# Sheet1.net
KiCad netlist of a schematic drawn in Altium Designer
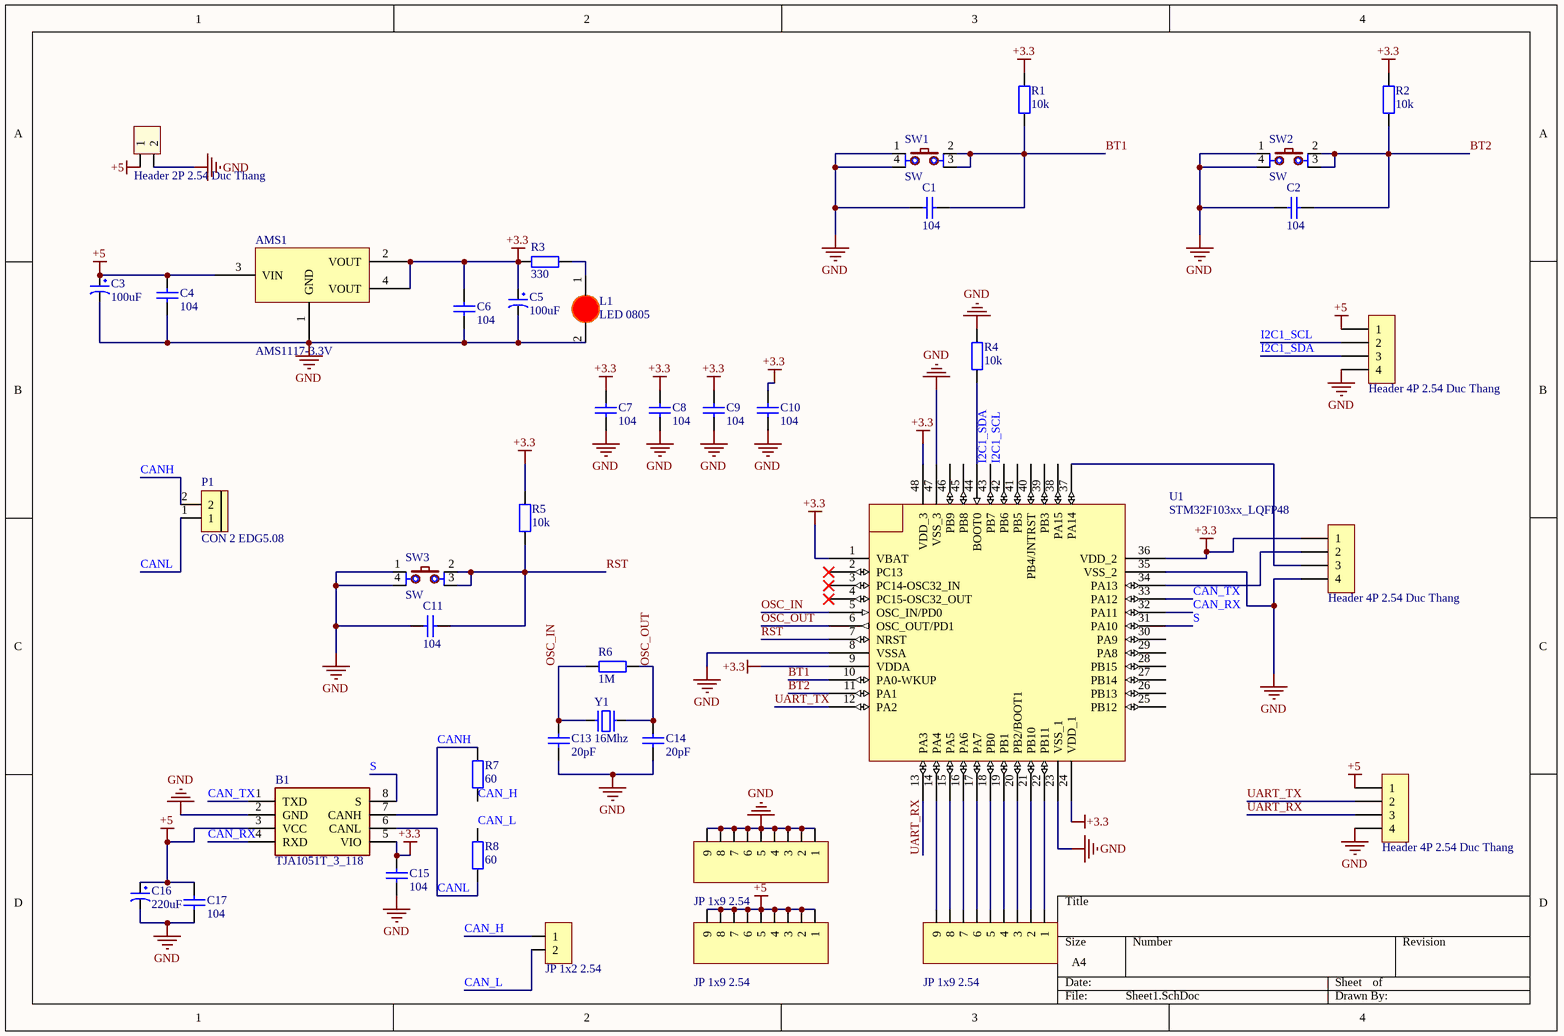
[diagram p0: Sheet1.SchDoc]

(export (version "E")
  (design (tool "Eeschema 10.0.6"))
  (components
    (comp (ref "AMS1")
      (value "AMS1117-3.3V")
      (footprint "SOT223")
      (description "Dán")
      (libsource (lib "Altium_Lib_by_KhueNguyenCreator") (part "AMS1117 SMD"))
    )
    (comp (ref "B1")
      (value "TJA1051T_3_118")
      (footprint "SOIC127P600X175-8N")
      (description "CAN Interface IC Hi Spd CAN Transcvr 4.5V-5.5V 250ns")
      (fields
        (field (name "MOUSER PART NUMBER") "771-TJA1051T3118")
        (field (name "MANUFACTURER_PART_NUMBER") "TJA1051T/3,118")
      )
      (libsource (lib "TJA1051T_3_118") (part "TJA1051T_3_118"))
    )
    (comp (ref "C1")
      (value "104")
      (footprint "tu 0805")
      (description "Dán")
      (libsource (lib "Altium_Lib_by_KhueNguyenCreator") (part "Tu 0805 104 50V 10%"))
    )
    (comp (ref "C2")
      (value "104")
      (footprint "tu 0805")
      (description "Dán")
      (libsource (lib "Altium_Lib_by_KhueNguyenCreator") (part "Tu 0805 104 50V 10%"))
    )
    (comp (ref "C3")
      (value "100uF")
      (footprint "tu hoa 5mm")
      (description "Cắm")
      (libsource (lib "Altium_Lib_by_KhueNguyenCreator") (part "Tu Hoa 100uF 16V 5x7"))
    )
    (comp (ref "C4")
      (value "104")
      (footprint "tu 0805")
      (description "Dán")
      (libsource (lib "Altium_Lib_by_KhueNguyenCreator") (part "Tu 0805 104 50V 10%"))
    )
    (comp (ref "C5")
      (value "100uF")
      (footprint "tu hoa 5mm")
      (description "Cắm")
      (libsource (lib "Altium_Lib_by_KhueNguyenCreator") (part "Tu Hoa 100uF 16V 5x7"))
    )
    (comp (ref "C6")
      (value "104")
      (footprint "tu 0805")
      (description "Dán")
      (libsource (lib "Altium_Lib_by_KhueNguyenCreator") (part "Tu 0805 104 50V 10%"))
    )
    (comp (ref "C7")
      (value "104")
      (footprint "tu 0805")
      (description "Dán")
      (libsource (lib "Altium_Lib_by_KhueNguyenCreator") (part "Tu 0805 104 50V 10%"))
    )
    (comp (ref "C8")
      (value "104")
      (footprint "tu 0805")
      (description "Dán")
      (libsource (lib "Altium_Lib_by_KhueNguyenCreator") (part "Tu 0805 104 50V 10%"))
    )
    (comp (ref "C9")
      (value "104")
      (footprint "tu 0805")
      (description "Dán")
      (libsource (lib "Altium_Lib_by_KhueNguyenCreator") (part "Tu 0805 104 50V 10%"))
    )
    (comp (ref "C10")
      (value "104")
      (footprint "tu 0805")
      (description "Dán")
      (libsource (lib "Altium_Lib_by_KhueNguyenCreator") (part "Tu 0805 104 50V 10%"))
    )
    (comp (ref "C11")
      (value "104")
      (footprint "tu 0805")
      (description "Dán")
      (libsource (lib "Altium_Lib_by_KhueNguyenCreator") (part "Tu 0805 104 50V 10%"))
    )
    (comp (ref "C13")
      (value "20pF")
      (footprint "tu 0805")
      (description "Dán")
      (libsource (lib "Altium_Lib_by_KhueNguyenCreator") (part "Tu 0805 104 50V 10%"))
    )
    (comp (ref "C14")
      (value "20pF")
      (footprint "tu 0805")
      (description "Dán")
      (libsource (lib "Altium_Lib_by_KhueNguyenCreator") (part "Tu 0805 104 50V 10%"))
    )
    (comp (ref "C15")
      (value "104")
      (footprint "tu 0805")
      (description "Dán")
      (libsource (lib "Altium_Lib_by_KhueNguyenCreator") (part "Tu 0805 104 50V 10%"))
    )
    (comp (ref "C16")
      (value "220uF")
      (footprint "tu hoa 16mm")
      (description "Cắm")
      (libsource (lib "Altium_Lib_by_KhueNguyenCreator") (part "Tu Hoa 220uF 200V 15x35"))
    )
    (comp (ref "C17")
      (value "104")
      (footprint "tu 0805")
      (description "Dán")
      (libsource (lib "Altium_Lib_by_KhueNguyenCreator") (part "Tu 0805 104 50V 10%"))
    )
    (comp (ref "H1")
      (value "Header 2P 2.54 Duc Thang")
      (footprint "XH2.54M-2")
      (description "Cắm")
      (libsource (lib "Altium_Lib_by_KhueNguyenCreator") (part "Header 2P 2.54 Duc Thang"))
    )
    (comp (ref "H2")
      (value "Header 4P 2.54 Duc Thang")
      (footprint "XH2.54M-4")
      (description "Cắm")
      (libsource (lib "Altium_Lib_by_KhueNguyenCreator") (part "Header 4P 2.54 Duc Thang"))
    )
    (comp (ref "H3")
      (value "Header 4P 2.54 Duc Thang")
      (footprint "XH2.54M-4")
      (description "Cắm")
      (libsource (lib "Altium_Lib_by_KhueNguyenCreator") (part "Header 4P 2.54 Duc Thang"))
    )
    (comp (ref "H4")
      (value "Header 4P 2.54 Duc Thang")
      (footprint "XH2.54M-4")
      (description "Cắm")
      (libsource (lib "Altium_Lib_by_KhueNguyenCreator") (part "Header 4P 2.54 Duc Thang"))
    )
    (comp (ref "JP1")
      (value "JP 1x9 2.54")
      (footprint "JP 1x9 DT")
      (description "Cắm")
      (libsource (lib "Altium_Lib_by_KhueNguyenCreator") (part "JP 1x9 2.54 Duc Thang"))
    )
    (comp (ref "JP2")
      (value "JP 1x9 2.54")
      (footprint "JP 1x9 DT")
      (description "Cắm")
      (libsource (lib "Altium_Lib_by_KhueNguyenCreator") (part "JP 1x9 2.54 Duc Thang"))
    )
    (comp (ref "JP3")
      (value "JP 1x9 2.54")
      (footprint "JP 1x9 DT")
      (description "Cắm")
      (libsource (lib "Altium_Lib_by_KhueNguyenCreator") (part "JP 1x9 2.54 Duc Thang"))
    )
    (comp (ref "JP5")
      (value "JP 1x2 2.54")
      (footprint "JP 1x2 DT")
      (description "Cắm")
      (libsource (lib "Altium_Lib_by_KhueNguyenCreator") (part "JP 1x2 2.54 Duc Thang"))
    )
    (comp (ref "L1")
      (value "LED 0805")
      (footprint "LED-0805-Red")
      (description "Dán")
      (libsource (lib "Altium_Lib_by_KhueNguyenCreator") (part "LED 0805 Do"))
    )
    (comp (ref "P1")
      (value "CON 2 EDG5.08")
      (footprint "CON 2 2EDG5.08")
      (description "Cắm")
      (libsource (lib "Altium_Lib_by_KhueNguyenCreator") (part "CON 2 EDG5.08"))
    )
    (comp (ref "R1")
      (value "10k")
      (footprint "tro smd 0805")
      (description "Dán")
      (libsource (lib "Altium_Lib_by_KhueNguyenCreator") (part "Tro 0805 1% 18k"))
    )
    (comp (ref "R2")
      (value "10k")
      (footprint "tro smd 0805")
      (description "Dán")
      (libsource (lib "Altium_Lib_by_KhueNguyenCreator") (part "Tro 0805 1% 18k"))
    )
    (comp (ref "R3")
      (value "330")
      (footprint "tro smd 0805")
      (description "Dán")
      (libsource (lib "Altium_Lib_by_KhueNguyenCreator") (part "Tro 0805 1% 18k"))
    )
    (comp (ref "R4")
      (value "10k")
      (footprint "tro smd 0805")
      (description "Dán")
      (libsource (lib "Altium_Lib_by_KhueNguyenCreator") (part "Tro 0805 1% 18k"))
    )
    (comp (ref "R5")
      (value "10k")
      (footprint "tro smd 0805")
      (description "Dán")
      (libsource (lib "Altium_Lib_by_KhueNguyenCreator") (part "Tro 0805 1% 18k"))
    )
    (comp (ref "R6")
      (value "1M")
      (footprint "tro smd 0805")
      (description "Dán")
      (libsource (lib "Altium_Lib_by_KhueNguyenCreator") (part "Tro 0805 1% 18k"))
    )
    (comp (ref "R7")
      (value "60")
      (footprint "tro smd 0805")
      (description "Dán")
      (libsource (lib "Altium_Lib_by_KhueNguyenCreator") (part "Tro 0805 1% 18k"))
    )
    (comp (ref "R8")
      (value "60")
      (footprint "tro smd 0805")
      (description "Dán")
      (libsource (lib "Altium_Lib_by_KhueNguyenCreator") (part "Tro 0805 1% 18k"))
    )
    (comp (ref "SW1")
      (value "SW")
      (footprint "SW2-DIP")
      (description "Switch button 4 pin")
      (libsource (lib "LIBRARY1") (part "SW4"))
    )
    (comp (ref "SW2")
      (value "SW")
      (footprint "SW2-DIP")
      (description "Switch button 4 pin")
      (libsource (lib "LIBRARY1") (part "SW4"))
    )
    (comp (ref "SW3")
      (value "SW")
      (footprint "SW2-DIP")
      (description "Switch button 4 pin")
      (libsource (lib "LIBRARY1") (part "SW4"))
    )
    (comp (ref "U1")
      (value "STM32F103xx_LQFP48")
      (footprint "STM32_LQPF48")
      (fields (field (name "PUBLISHER") "Altium Limited"))
      (libsource (lib "Altium_Lib_by_KhueNguyenCreator") (part "STM32F103xx_LQFP48"))
    )
    (comp (ref "Y1")
      (value "16Mhz")
      (footprint "Thach Anh 2 chan cam")
      (description "Crystal For all Crystal 2pin.")
      (libsource (lib "Altium_Lib_by_KhueNguyenCreator") (part "Thach Anh 2 chan Cam"))
    )
  )
  (nets
    (net (code "1") (name "+3.3") (class "Default")
      (node (ref "AMS1") (pin "2") (pinfunction "VOUT_2") (pintype "passive"))
      (node (ref "AMS1") (pin "4") (pinfunction "VOUT_4") (pintype "passive"))
      (node (ref "B1") (pin "5") (pinfunction "VIO_5") (pintype "passive"))
      (node (ref "C10") (pin "1") (pinfunction "1_1") (pintype "passive"))
      (node (ref "C15") (pin "1") (pinfunction "1_1") (pintype "passive"))
      (node (ref "C5") (pin "1") (pinfunction "1_1") (pintype "passive"))
      (node (ref "C6") (pin "1") (pinfunction "1_1") (pintype "passive"))
      (node (ref "C7") (pin "1") (pinfunction "1_1") (pintype "passive"))
      (node (ref "C8") (pin "1") (pinfunction "1_1") (pintype "passive"))
      (node (ref "C9") (pin "1") (pinfunction "1_1") (pintype "passive"))
      (node (ref "H3") (pin "1") (pinfunction "1_1") (pintype "passive"))
      (node (ref "R1") (pin "2") (pinfunction "2_2") (pintype "passive"))
      (node (ref "R2") (pin "2") (pinfunction "2_2") (pintype "passive"))
      (node (ref "R3") (pin "2") (pinfunction "2_2") (pintype "passive"))
      (node (ref "R5") (pin "2") (pinfunction "2_2") (pintype "passive"))
      (node (ref "U1") (pin "1") (pinfunction "VBAT_1") (pintype "power_in"))
      (node (ref "U1") (pin "24") (pinfunction "VDD_1_24") (pintype "power_in"))
      (node (ref "U1") (pin "36") (pinfunction "VDD_2_36") (pintype "power_in"))
      (node (ref "U1") (pin "48") (pinfunction "VDD_3_48") (pintype "power_in"))
      (node (ref "U1") (pin "9") (pinfunction "VDDA_9") (pintype "power_in"))
    )
    (net (code "2") (name "+5") (class "Default")
      (node (ref "AMS1") (pin "3") (pinfunction "VIN_3") (pintype "passive"))
      (node (ref "B1") (pin "3") (pinfunction "VCC_3") (pintype "passive"))
      (node (ref "C16") (pin "1") (pinfunction "1_1") (pintype "passive"))
      (node (ref "C17") (pin "1") (pinfunction "1_1") (pintype "passive"))
      (node (ref "C3") (pin "1") (pinfunction "1_1") (pintype "passive"))
      (node (ref "C4") (pin "1") (pinfunction "1_1") (pintype "passive"))
      (node (ref "H1") (pin "1") (pinfunction "1_1") (pintype "passive"))
      (node (ref "H2") (pin "1") (pinfunction "1_1") (pintype "passive"))
      (node (ref "H4") (pin "1") (pinfunction "1_1") (pintype "passive"))
      (node (ref "JP3") (pin "1") (pinfunction "1_1") (pintype "passive"))
      (node (ref "JP3") (pin "2") (pinfunction "2_2") (pintype "passive"))
      (node (ref "JP3") (pin "3") (pinfunction "3_3") (pintype "passive"))
      (node (ref "JP3") (pin "4") (pinfunction "4_4") (pintype "passive"))
      (node (ref "JP3") (pin "5") (pinfunction "5_5") (pintype "passive"))
      (node (ref "JP3") (pin "6") (pinfunction "6_6") (pintype "passive"))
      (node (ref "JP3") (pin "7") (pinfunction "7_7") (pintype "passive"))
      (node (ref "JP3") (pin "8") (pinfunction "8_8") (pintype "passive"))
      (node (ref "JP3") (pin "9") (pinfunction "9_9") (pintype "passive"))
    )
    (net (code "3") (name "/BT1") (class "Default")
      (node (ref "C1") (pin "2") (pinfunction "2_2") (pintype "passive"))
      (node (ref "R1") (pin "1") (pinfunction "1_1") (pintype "passive"))
      (node (ref "SW1") (pin "2") (pinfunction "2_2") (pintype "passive"))
      (node (ref "SW1") (pin "3") (pinfunction "3_3") (pintype "passive"))
      (node (ref "U1") (pin "10") (pinfunction "PA0-WKUP_10") (pintype "bidirectional"))
    )
    (net (code "4") (name "/BT2") (class "Default")
      (node (ref "C2") (pin "2") (pinfunction "2_2") (pintype "passive"))
      (node (ref "R2") (pin "1") (pinfunction "1_1") (pintype "passive"))
      (node (ref "SW2") (pin "2") (pinfunction "2_2") (pintype "passive"))
      (node (ref "SW2") (pin "3") (pinfunction "3_3") (pintype "passive"))
      (node (ref "U1") (pin "11") (pinfunction "PA1_11") (pintype "bidirectional"))
    )
    (net (code "5") (name "/CANH") (class "Default")
      (node (ref "B1") (pin "7") (pinfunction "CANH_7") (pintype "passive"))
      (node (ref "P1") (pin "2") (pinfunction "2_2") (pintype "passive"))
      (node (ref "R7") (pin "2") (pinfunction "2_2") (pintype "passive"))
    )
    (net (code "6") (name "/CANL") (class "Default")
      (node (ref "B1") (pin "6") (pinfunction "CANL_6") (pintype "passive"))
      (node (ref "P1") (pin "1") (pinfunction "1_1") (pintype "passive"))
      (node (ref "R8") (pin "1") (pinfunction "1_1") (pintype "passive"))
    )
    (net (code "7") (name "/CAN_H") (class "Default")
      (node (ref "JP5") (pin "1") (pinfunction "1_1") (pintype "passive"))
      (node (ref "R7") (pin "1") (pinfunction "1_1") (pintype "passive"))
    )
    (net (code "8") (name "/CAN_L") (class "Default")
      (node (ref "JP5") (pin "2") (pinfunction "2_2") (pintype "passive"))
      (node (ref "R8") (pin "2") (pinfunction "2_2") (pintype "passive"))
    )
    (net (code "9") (name "/CAN_RX") (class "Default")
      (node (ref "B1") (pin "4") (pinfunction "RXD_4") (pintype "passive"))
      (node (ref "U1") (pin "32") (pinfunction "PA11_32") (pintype "bidirectional"))
    )
    (net (code "10") (name "/CAN_TX") (class "Default")
      (node (ref "B1") (pin "1") (pinfunction "TXD_1") (pintype "passive"))
      (node (ref "U1") (pin "33") (pinfunction "PA12_33") (pintype "bidirectional"))
    )
    (net (code "11") (name "/I2C1_SCL") (class "Default")
      (node (ref "H2") (pin "2") (pinfunction "2_2") (pintype "passive"))
      (node (ref "U1") (pin "42") (pinfunction "PB6_42") (pintype "bidirectional"))
    )
    (net (code "12") (name "/I2C1_SDA") (class "Default")
      (node (ref "H2") (pin "3") (pinfunction "3_3") (pintype "passive"))
      (node (ref "U1") (pin "43") (pinfunction "PB7_43") (pintype "bidirectional"))
    )
    (net (code "13") (name "/OSC_IN") (class "Default")
      (node (ref "C13") (pin "1") (pinfunction "1_1") (pintype "passive"))
      (node (ref "R6") (pin "2") (pinfunction "2_2") (pintype "passive"))
      (node (ref "U1") (pin "5") (pinfunction "OSC_IN/PD0_5") (pintype "input"))
      (node (ref "Y1") (pin "1") (pinfunction "1_1") (pintype "passive"))
    )
    (net (code "14") (name "/OSC_OUT") (class "Default")
      (node (ref "C14") (pin "1") (pinfunction "1_1") (pintype "passive"))
      (node (ref "R6") (pin "1") (pinfunction "1_1") (pintype "passive"))
      (node (ref "U1") (pin "6") (pinfunction "OSC_OUT/PD1_6") (pintype "output"))
      (node (ref "Y1") (pin "2") (pinfunction "2_2") (pintype "passive"))
    )
    (net (code "15") (name "/RST") (class "Default")
      (node (ref "C11") (pin "2") (pinfunction "2_2") (pintype "passive"))
      (node (ref "R5") (pin "1") (pinfunction "1_1") (pintype "passive"))
      (node (ref "SW3") (pin "2") (pinfunction "2_2") (pintype "passive"))
      (node (ref "SW3") (pin "3") (pinfunction "3_3") (pintype "passive"))
      (node (ref "U1") (pin "7") (pinfunction "NRST_7") (pintype "bidirectional"))
    )
    (net (code "16") (name "/S") (class "Default")
      (node (ref "B1") (pin "8") (pinfunction "S_8") (pintype "passive"))
      (node (ref "U1") (pin "31") (pinfunction "PA10_31") (pintype "bidirectional"))
    )
    (net (code "17") (name "/UART_RX") (class "Default")
      (node (ref "H4") (pin "3") (pinfunction "3_3") (pintype "passive"))
      (node (ref "U1") (pin "13") (pinfunction "PA3_13") (pintype "bidirectional"))
    )
    (net (code "18") (name "/UART_TX") (class "Default")
      (node (ref "H4") (pin "2") (pinfunction "2_2") (pintype "passive"))
      (node (ref "U1") (pin "12") (pinfunction "PA2_12") (pintype "bidirectional"))
    )
    (net (code "19") (name "GND") (class "Default")
      (node (ref "AMS1") (pin "1") (pinfunction "GND_1") (pintype "passive"))
      (node (ref "B1") (pin "2") (pinfunction "GND_2") (pintype "passive"))
      (node (ref "C1") (pin "1") (pinfunction "1_1") (pintype "passive"))
      (node (ref "C10") (pin "2") (pinfunction "2_2") (pintype "passive"))
      (node (ref "C11") (pin "1") (pinfunction "1_1") (pintype "passive"))
      (node (ref "C13") (pin "2") (pinfunction "2_2") (pintype "passive"))
      (node (ref "C14") (pin "2") (pinfunction "2_2") (pintype "passive"))
      (node (ref "C15") (pin "2") (pinfunction "2_2") (pintype "passive"))
      (node (ref "C16") (pin "2") (pinfunction "2_2") (pintype "passive"))
      (node (ref "C17") (pin "2") (pinfunction "2_2") (pintype "passive"))
      (node (ref "C2") (pin "1") (pinfunction "1_1") (pintype "passive"))
      (node (ref "C3") (pin "2") (pinfunction "2_2") (pintype "passive"))
      (node (ref "C4") (pin "2") (pinfunction "2_2") (pintype "passive"))
      (node (ref "C5") (pin "2") (pinfunction "2_2") (pintype "passive"))
      (node (ref "C6") (pin "2") (pinfunction "2_2") (pintype "passive"))
      (node (ref "C7") (pin "2") (pinfunction "2_2") (pintype "passive"))
      (node (ref "C8") (pin "2") (pinfunction "2_2") (pintype "passive"))
      (node (ref "C9") (pin "2") (pinfunction "2_2") (pintype "passive"))
      (node (ref "H1") (pin "2") (pinfunction "2_2") (pintype "passive"))
      (node (ref "H2") (pin "4") (pinfunction "4_4") (pintype "passive"))
      (node (ref "H3") (pin "4") (pinfunction "4_4") (pintype "passive"))
      (node (ref "H4") (pin "4") (pinfunction "4_4") (pintype "passive"))
      (node (ref "JP2") (pin "1") (pinfunction "1_1") (pintype "passive"))
      (node (ref "JP2") (pin "2") (pinfunction "2_2") (pintype "passive"))
      (node (ref "JP2") (pin "3") (pinfunction "3_3") (pintype "passive"))
      (node (ref "JP2") (pin "4") (pinfunction "4_4") (pintype "passive"))
      (node (ref "JP2") (pin "5") (pinfunction "5_5") (pintype "passive"))
      (node (ref "JP2") (pin "6") (pinfunction "6_6") (pintype "passive"))
      (node (ref "JP2") (pin "7") (pinfunction "7_7") (pintype "passive"))
      (node (ref "JP2") (pin "8") (pinfunction "8_8") (pintype "passive"))
      (node (ref "JP2") (pin "9") (pinfunction "9_9") (pintype "passive"))
      (node (ref "L1") (pin "2") (pinfunction "K_2") (pintype "passive"))
      (node (ref "R4") (pin "2") (pinfunction "2_2") (pintype "passive"))
      (node (ref "SW1") (pin "1") (pintype "passive"))
      (node (ref "SW1") (pin "4") (pinfunction "4_4") (pintype "passive"))
      (node (ref "SW2") (pin "1") (pintype "passive"))
      (node (ref "SW2") (pin "4") (pinfunction "4_4") (pintype "passive"))
      (node (ref "SW3") (pin "1") (pintype "passive"))
      (node (ref "SW3") (pin "4") (pinfunction "4_4") (pintype "passive"))
      (node (ref "U1") (pin "23") (pinfunction "VSS_1_23") (pintype "power_in"))
      (node (ref "U1") (pin "35") (pinfunction "VSS_2_35") (pintype "power_in"))
      (node (ref "U1") (pin "47") (pinfunction "VSS_3_47") (pintype "power_in"))
      (node (ref "U1") (pin "8") (pinfunction "VSSA_8") (pintype "power_in"))
    )
    (net (code "20") (name "Net-(L1-A)") (class "Default")
      (node (ref "L1") (pin "1") (pinfunction "A_1") (pintype "passive"))
      (node (ref "R3") (pin "1") (pinfunction "1_1") (pintype "passive"))
    )
    (net (code "21") (name "Net-(U1-BOOT0)") (class "Default")
      (node (ref "R4") (pin "1") (pinfunction "1_1") (pintype "passive"))
      (node (ref "U1") (pin "44") (pinfunction "BOOT0_44") (pintype "input"))
    )
    (net (code "22") (name "Net-(U1-PA4)") (class "Default")
      (node (ref "JP1") (pin "9") (pinfunction "9_9") (pintype "passive"))
      (node (ref "U1") (pin "14") (pinfunction "PA4_14") (pintype "bidirectional"))
    )
    (net (code "23") (name "Net-(U1-PA5)") (class "Default")
      (node (ref "JP1") (pin "8") (pinfunction "8_8") (pintype "passive"))
      (node (ref "U1") (pin "15") (pinfunction "PA5_15") (pintype "bidirectional"))
    )
    (net (code "24") (name "Net-(U1-PA6)") (class "Default")
      (node (ref "JP1") (pin "7") (pinfunction "7_7") (pintype "passive"))
      (node (ref "U1") (pin "16") (pinfunction "PA6_16") (pintype "bidirectional"))
    )
    (net (code "25") (name "Net-(U1-PA7)") (class "Default")
      (node (ref "JP1") (pin "6") (pinfunction "6_6") (pintype "passive"))
      (node (ref "U1") (pin "17") (pinfunction "PA7_17") (pintype "bidirectional"))
    )
    (net (code "26") (name "Net-(U1-PA13)") (class "Default")
      (node (ref "H3") (pin "2") (pinfunction "2_2") (pintype "passive"))
      (node (ref "U1") (pin "34") (pinfunction "PA13_34") (pintype "bidirectional"))
    )
    (net (code "27") (name "Net-(U1-PA14)") (class "Default")
      (node (ref "H3") (pin "3") (pinfunction "3_3") (pintype "passive"))
      (node (ref "U1") (pin "37") (pinfunction "PA14_37") (pintype "bidirectional"))
    )
    (net (code "28") (name "Net-(U1-PB0)") (class "Default")
      (node (ref "JP1") (pin "5") (pinfunction "5_5") (pintype "passive"))
      (node (ref "U1") (pin "18") (pinfunction "PB0_18") (pintype "bidirectional"))
    )
    (net (code "29") (name "Net-(U1-PB1)") (class "Default")
      (node (ref "JP1") (pin "4") (pinfunction "4_4") (pintype "passive"))
      (node (ref "U1") (pin "19") (pinfunction "PB1_19") (pintype "bidirectional"))
    )
    (net (code "30") (name "Net-(U1-PB2{slash}BOOT1)") (class "Default")
      (node (ref "JP1") (pin "3") (pinfunction "3_3") (pintype "passive"))
      (node (ref "U1") (pin "20") (pinfunction "PB2/BOOT1_20") (pintype "bidirectional"))
    )
    (net (code "31") (name "Net-(U1-PB10)") (class "Default")
      (node (ref "JP1") (pin "2") (pinfunction "2_2") (pintype "passive"))
      (node (ref "U1") (pin "21") (pinfunction "PB10_21") (pintype "bidirectional"))
    )
    (net (code "32") (name "Net-(U1-PB11)") (class "Default")
      (node (ref "JP1") (pin "1") (pinfunction "1_1") (pintype "passive"))
      (node (ref "U1") (pin "22") (pinfunction "PB11_22") (pintype "bidirectional"))
    )
    (net (code "33") (name "unconnected-(U1-PA8-Pad29)") (class "Default")
      (node (ref "U1") (pin "29") (pinfunction "PA8_29") (pintype "bidirectional"))
    )
    (net (code "34") (name "unconnected-(U1-PA9-Pad30)") (class "Default")
      (node (ref "U1") (pin "30") (pinfunction "PA9_30") (pintype "bidirectional"))
    )
    (net (code "35") (name "unconnected-(U1-PA15-Pad38)") (class "Default")
      (node (ref "U1") (pin "38") (pinfunction "PA15_38") (pintype "bidirectional"))
    )
    (net (code "36") (name "unconnected-(U1-PB3-Pad39)") (class "Default")
      (node (ref "U1") (pin "39") (pinfunction "PB3_39") (pintype "bidirectional"))
    )
    (net (code "37") (name "unconnected-(U1-PB4{slash}JNTRST-Pad40)") (class "Default")
      (node (ref "U1") (pin "40") (pinfunction "PB4/JNTRST_40") (pintype "bidirectional"))
    )
    (net (code "38") (name "unconnected-(U1-PB5-Pad41)") (class "Default")
      (node (ref "U1") (pin "41") (pinfunction "PB5_41") (pintype "bidirectional"))
    )
    (net (code "39") (name "unconnected-(U1-PB8-Pad45)") (class "Default")
      (node (ref "U1") (pin "45") (pinfunction "PB8_45") (pintype "bidirectional"))
    )
    (net (code "40") (name "unconnected-(U1-PB9-Pad46)") (class "Default")
      (node (ref "U1") (pin "46") (pinfunction "PB9_46") (pintype "bidirectional"))
    )
    (net (code "41") (name "unconnected-(U1-PB12-Pad25)") (class "Default")
      (node (ref "U1") (pin "25") (pinfunction "PB12_25") (pintype "bidirectional"))
    )
    (net (code "42") (name "unconnected-(U1-PB13-Pad26)") (class "Default")
      (node (ref "U1") (pin "26") (pinfunction "PB13_26") (pintype "bidirectional"))
    )
    (net (code "43") (name "unconnected-(U1-PB14-Pad27)") (class "Default")
      (node (ref "U1") (pin "27") (pinfunction "PB14_27") (pintype "bidirectional"))
    )
    (net (code "44") (name "unconnected-(U1-PB15-Pad28)") (class "Default")
      (node (ref "U1") (pin "28") (pinfunction "PB15_28") (pintype "bidirectional"))
    )
    (net (code "45") (name "unconnected-(U1-PC13-Pad2)") (class "Default")
      (node (ref "U1") (pin "2") (pinfunction "PC13_2") (pintype "bidirectional+no_connect"))
    )
    (net (code "46") (name "unconnected-(U1-PC14-OSC32_IN-Pad3)") (class "Default")
      (node (ref "U1") (pin "3") (pinfunction "PC14-OSC32_IN_3") (pintype "bidirectional+no_connect"))
    )
    (net (code "47") (name "unconnected-(U1-PC15-OSC32_OUT-Pad4)") (class "Default")
      (node (ref "U1") (pin "4") (pinfunction "PC15-OSC32_OUT_4") (pintype "bidirectional+no_connect"))
    )
  )
)
